# fantom_power.net
KiCad netlist of a schematic drawn in Altium Designer
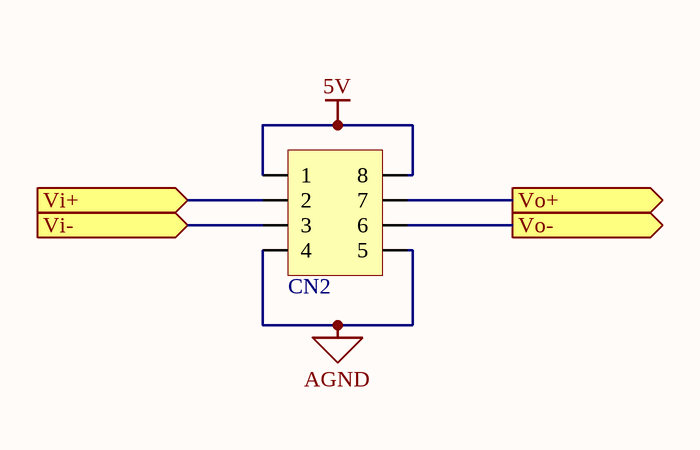
[diagram p0: fantom_power.SchDoc]

(export (version "E")
  (design (tool "Eeschema 10.0.6"))
  (components
    (comp (ref "CN2")
      (value "Header 4X2")
      (footprint "Pcb_Conectores:Header 4x2")
      (libsource (lib "Sch_Conectores") (part "Header 4X2"))
    )
  )
  (nets
    (net (code "1") (name "/Vi+") (class "Default")
      (node (ref "CN2") (pin "2") (pinfunction "2_2") (pintype "passive"))
    )
    (net (code "2") (name "/Vi-") (class "Default")
      (node (ref "CN2") (pin "3") (pinfunction "3_3") (pintype "passive"))
    )
    (net (code "3") (name "/Vo+") (class "Default")
      (node (ref "CN2") (pin "7") (pinfunction "7_7") (pintype "passive"))
    )
    (net (code "4") (name "/Vo-") (class "Default")
      (node (ref "CN2") (pin "6") (pinfunction "6_6") (pintype "passive"))
    )
    (net (code "5") (name "5V") (class "Default")
      (node (ref "CN2") (pin "1") (pinfunction "1_1") (pintype "passive"))
      (node (ref "CN2") (pin "8") (pinfunction "8_8") (pintype "passive"))
    )
    (net (code "6") (name "AGND") (class "Default")
      (node (ref "CN2") (pin "4") (pinfunction "4_4") (pintype "passive"))
      (node (ref "CN2") (pin "5") (pinfunction "5_5") (pintype "passive"))
    )
  )
)
